# v0_1.net
KiCad netlist of a schematic drawn in EAGLE
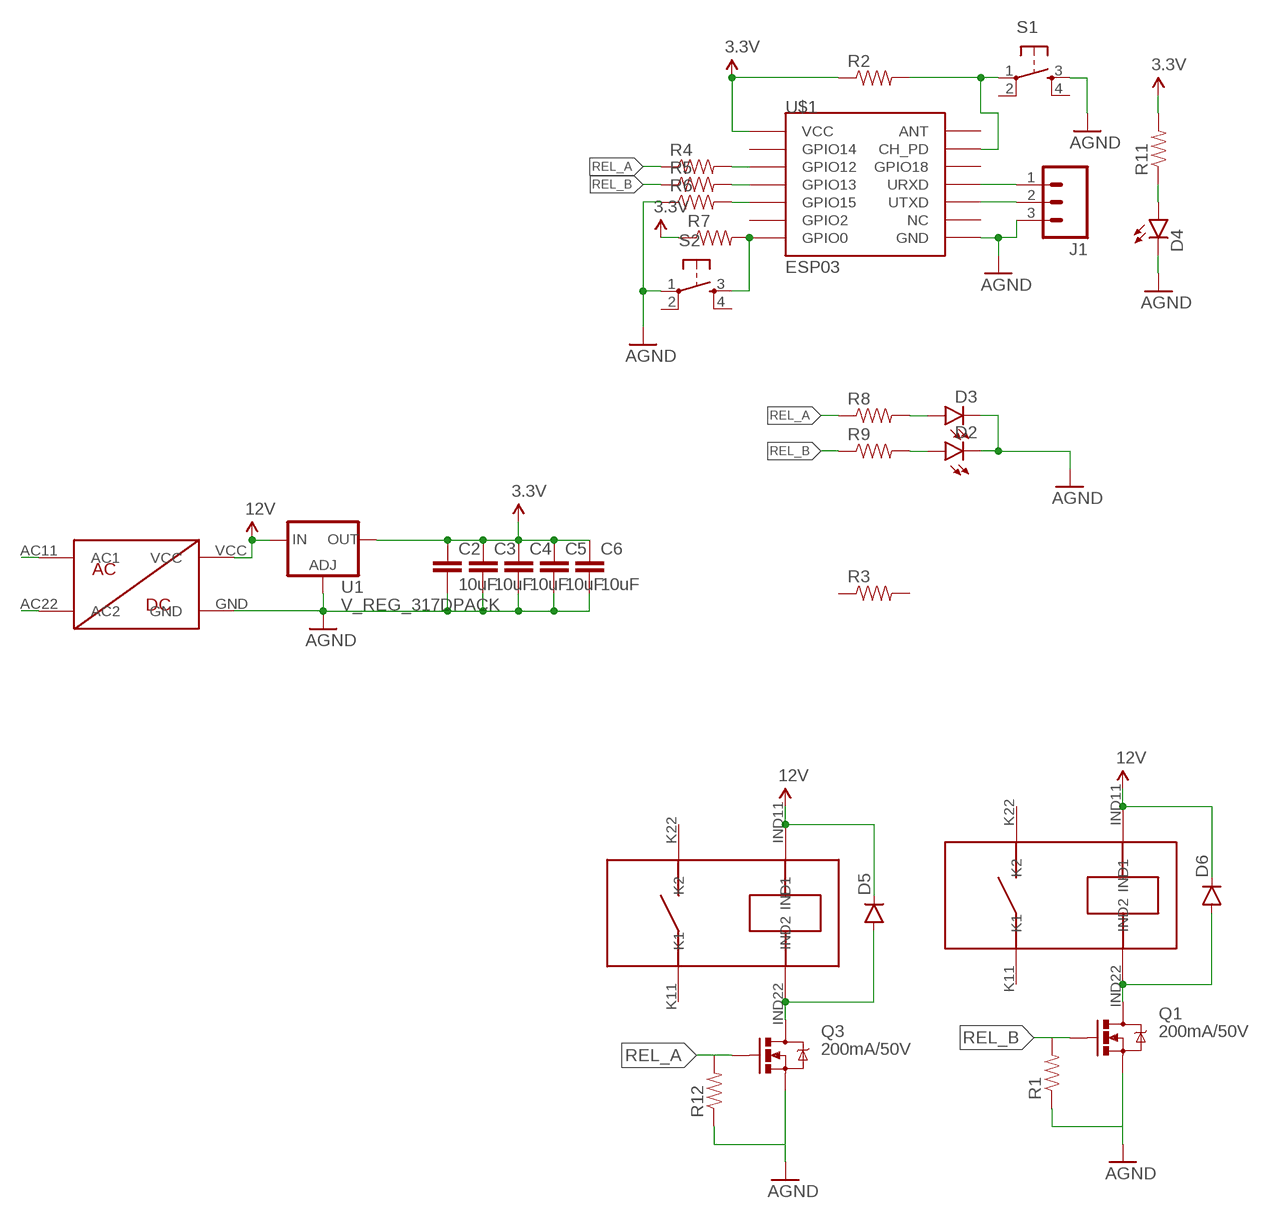
[diagram p0: schematic, sheet 1]

(export (version "E")
  (design (tool "Eeschema 10.0.6"))
  (components
    (comp (ref "C2")
      (value "10uF")
      (footprint "eagle-import:0603-CAP")
      (libsource (lib "eagle-import") (part "10UF-6.3V-20%(0603)"))
    )
    (comp (ref "C3")
      (value "10uF")
      (footprint "eagle-import:0603-CAP")
      (libsource (lib "eagle-import") (part "10UF-6.3V-20%(0603)"))
    )
    (comp (ref "C4")
      (value "10uF")
      (footprint "eagle-import:0603-CAP")
      (libsource (lib "eagle-import") (part "10UF-6.3V-20%(0603)"))
    )
    (comp (ref "C5")
      (value "10uF")
      (footprint "eagle-import:0603-CAP")
      (libsource (lib "eagle-import") (part "10UF-6.3V-20%(0603)"))
    )
    (comp (ref "C6")
      (value "10uF")
      (footprint "eagle-import:0603-CAP")
      (libsource (lib "eagle-import") (part "10UF-6.3V-20%(0603)"))
    )
    (comp (ref "D2")
      (value "LED0603")
      (footprint "eagle-import:LED-0603")
      (libsource (lib "eagle-import") (part "LED0603"))
    )
    (comp (ref "D3")
      (value "LED0603")
      (footprint "eagle-import:LED-0603")
      (libsource (lib "eagle-import") (part "LED0603"))
    )
    (comp (ref "D4")
      (value "LED0603")
      (footprint "eagle-import:LED-0603")
      (libsource (lib "eagle-import") (part "LED0603"))
    )
    (comp (ref "D5")
      (value "DIODESOD123")
      (footprint "eagle-import:SOD-123")
      (libsource (lib "eagle-import") (part "DIODESOD123"))
    )
    (comp (ref "D6")
      (value "DIODESOD123")
      (footprint "eagle-import:SOD-123")
      (libsource (lib "eagle-import") (part "DIODESOD123"))
    )
    (comp (ref "J1")
      (value "M03LONGPADS")
      (footprint "eagle-import:1X03_LONGPADS")
      (libsource (lib "eagle-import") (part "M03LONGPADS"))
    )
    (comp (ref "Q1")
      (value "200mA/50V")
      (footprint "eagle-import:SOT23-3")
      (libsource (lib "eagle-import") (part "MOSFET-NCHANNELBSS138"))
    )
    (comp (ref "Q3")
      (value "200mA/50V")
      (footprint "eagle-import:SOT23-3")
      (libsource (lib "eagle-import") (part "MOSFET-NCHANNELBSS138"))
    )
    (comp (ref "R1")
      (value "RESISTOR0805-RES")
      (footprint "eagle-import:0805")
      (libsource (lib "eagle-import") (part "RESISTOR0805-RES"))
    )
    (comp (ref "R2")
      (value "RESISTOR0805-RES")
      (footprint "eagle-import:0805")
      (libsource (lib "eagle-import") (part "RESISTOR0805-RES"))
    )
    (comp (ref "R3")
      (value "RESISTOR0805-RES")
      (footprint "eagle-import:0805")
      (libsource (lib "eagle-import") (part "RESISTOR0805-RES"))
    )
    (comp (ref "R4")
      (value "RESISTOR0805-RES")
      (footprint "eagle-import:0805")
      (libsource (lib "eagle-import") (part "RESISTOR0805-RES"))
    )
    (comp (ref "R5")
      (value "RESISTOR0805-RES")
      (footprint "eagle-import:0805")
      (libsource (lib "eagle-import") (part "RESISTOR0805-RES"))
    )
    (comp (ref "R6")
      (value "RESISTOR0805-RES")
      (footprint "eagle-import:0805")
      (libsource (lib "eagle-import") (part "RESISTOR0805-RES"))
    )
    (comp (ref "R7")
      (value "RESISTOR0805-RES")
      (footprint "eagle-import:0805")
      (libsource (lib "eagle-import") (part "RESISTOR0805-RES"))
    )
    (comp (ref "R8")
      (value "RESISTOR0805-RES")
      (footprint "eagle-import:0805")
      (libsource (lib "eagle-import") (part "RESISTOR0805-RES"))
    )
    (comp (ref "R9")
      (value "RESISTOR0805-RES")
      (footprint "eagle-import:0805")
      (libsource (lib "eagle-import") (part "RESISTOR0805-RES"))
    )
    (comp (ref "R11")
      (value "RESISTOR0805-RES")
      (footprint "eagle-import:0805")
      (libsource (lib "eagle-import") (part "RESISTOR0805-RES"))
    )
    (comp (ref "R12")
      (value "RESISTOR0805-RES")
      (footprint "eagle-import:0805")
      (libsource (lib "eagle-import") (part "RESISTOR0805-RES"))
    )
    (comp (ref "S1")
      (value "TAC_SWITCHPTH")
      (footprint "eagle-import:TACTILE-PTH")
      (libsource (lib "eagle-import") (part "TAC_SWITCHPTH"))
    )
    (comp (ref "S2")
      (value "TAC_SWITCHPTH")
      (footprint "eagle-import:TACTILE-PTH")
      (libsource (lib "eagle-import") (part "TAC_SWITCHPTH"))
    )
    (comp (ref "U$1")
      (value "ESP03")
      (footprint "eagle-import:ESP03")
      (libsource (lib "eagle-import") (part "ESP03"))
    )
    (comp (ref "U$8")
      (value "ACDC12V350MA")
      (footprint "eagle-import:ACDC12V350MA")
      (libsource (lib "eagle-import") (part "ACDC12V350MA"))
    )
    (comp (ref "U$9")
      (value "302WP")
      (footprint "eagle-import:302WP")
      (libsource (lib "eagle-import") (part "302WP"))
    )
    (comp (ref "U$10")
      (value "302WP")
      (footprint "eagle-import:302WP")
      (libsource (lib "eagle-import") (part "302WP"))
    )
    (comp (ref "U1")
      (value "V_REG_317DPACK")
      (footprint "eagle-import:V-REG_DPACK")
      (libsource (lib "eagle-import") (part "V_REG_317DPACK"))
    )
  )
  (nets
    (net (code "1") (name "3.3V") (class "Default")
      (node (ref "C2") (pin "1") (pinfunction "1_1") (pintype "passive"))
      (node (ref "C3") (pin "1") (pinfunction "1_1") (pintype "passive"))
      (node (ref "C4") (pin "1") (pinfunction "1_1") (pintype "passive"))
      (node (ref "C5") (pin "1") (pinfunction "1_1") (pintype "passive"))
      (node (ref "C6") (pin "1") (pinfunction "1_1") (pintype "passive"))
      (node (ref "R11") (pin "2") (pinfunction "2_2") (pintype "passive"))
      (node (ref "R2") (pin "1") (pinfunction "1_1") (pintype "passive"))
      (node (ref "R7") (pin "1") (pinfunction "1_1") (pintype "passive"))
      (node (ref "U$1") (pin "VCC") (pinfunction "VCC_VCC") (pintype "bidirectional"))
      (node (ref "U1") (pin "4") (pinfunction "OUT_4") (pintype "output"))
    )
    (net (code "2") (name "12V") (class "Default")
      (node (ref "D5") (pin "C") (pinfunction "C_C") (pintype "passive"))
      (node (ref "D6") (pin "C") (pinfunction "C_C") (pintype "passive"))
      (node (ref "U$10") (pin "IND11") (pinfunction "IND1_IND11") (pintype "bidirectional"))
      (node (ref "U$8") (pin "VCC") (pinfunction "VCC_VCC") (pintype "bidirectional"))
      (node (ref "U$9") (pin "IND11") (pinfunction "IND1_IND11") (pintype "bidirectional"))
      (node (ref "U1") (pin "3") (pinfunction "IN_3") (pintype "input"))
    )
    (net (code "3") (name "AGND") (class "Default")
      (node (ref "C2") (pin "2") (pinfunction "2_2") (pintype "passive"))
      (node (ref "C3") (pin "2") (pinfunction "2_2") (pintype "passive"))
      (node (ref "C4") (pin "2") (pinfunction "2_2") (pintype "passive"))
      (node (ref "C5") (pin "2") (pinfunction "2_2") (pintype "passive"))
      (node (ref "C6") (pin "2") (pinfunction "2_2") (pintype "passive"))
      (node (ref "D2") (pin "C") (pinfunction "C_C") (pintype "passive"))
      (node (ref "D3") (pin "C") (pinfunction "C_C") (pintype "passive"))
      (node (ref "D4") (pin "C") (pinfunction "C_C") (pintype "passive"))
      (node (ref "J1") (pin "3") (pinfunction "3_3") (pintype "passive"))
      (node (ref "Q1") (pin "2") (pinfunction "S_2") (pintype "passive"))
      (node (ref "Q3") (pin "2") (pinfunction "S_2") (pintype "passive"))
      (node (ref "R1") (pin "1") (pinfunction "1_1") (pintype "passive"))
      (node (ref "R12") (pin "1") (pinfunction "1_1") (pintype "passive"))
      (node (ref "R6") (pin "1") (pinfunction "1_1") (pintype "passive"))
      (node (ref "S1") (pin "3") (pinfunction "3_3") (pintype "passive"))
      (node (ref "S2") (pin "1") (pinfunction "1_1") (pintype "passive"))
      (node (ref "U$1") (pin "GND") (pinfunction "GND_GND") (pintype "bidirectional"))
      (node (ref "U$8") (pin "GND") (pinfunction "GND_GND") (pintype "bidirectional"))
      (node (ref "U1") (pin "1") (pinfunction "ADJ_1") (pintype "input"))
    )
    (net (code "4") (name "Net-(D2-PadA)") (class "Default")
      (node (ref "D2") (pin "A") (pinfunction "A_A") (pintype "passive"))
      (node (ref "R9") (pin "2") (pinfunction "2_2") (pintype "passive"))
    )
    (net (code "5") (name "Net-(D3-PadA)") (class "Default")
      (node (ref "D3") (pin "A") (pinfunction "A_A") (pintype "passive"))
      (node (ref "R8") (pin "2") (pinfunction "2_2") (pintype "passive"))
    )
    (net (code "6") (name "Net-(D4-PadA)") (class "Default")
      (node (ref "D4") (pin "A") (pinfunction "A_A") (pintype "passive"))
      (node (ref "R11") (pin "1") (pinfunction "1_1") (pintype "passive"))
    )
    (net (code "7") (name "Net-(J1-Pad1)") (class "Default")
      (node (ref "J1") (pin "1") (pinfunction "1_1") (pintype "passive"))
      (node (ref "U$1") (pin "URXD") (pinfunction "URXD_URXD") (pintype "bidirectional"))
    )
    (net (code "8") (name "Net-(J1-Pad2)") (class "Default")
      (node (ref "J1") (pin "2") (pinfunction "2_2") (pintype "passive"))
      (node (ref "U$1") (pin "UTXD") (pinfunction "UTXD_UTXD") (pintype "bidirectional"))
    )
    (net (code "9") (name "Net-(Q1-D)") (class "Default")
      (node (ref "D6") (pin "A") (pinfunction "A_A") (pintype "passive"))
      (node (ref "Q1") (pin "3") (pinfunction "D_3") (pintype "passive"))
      (node (ref "U$9") (pin "IND22") (pinfunction "IND2_IND22") (pintype "bidirectional"))
    )
    (net (code "10") (name "Net-(Q3-D)") (class "Default")
      (node (ref "D5") (pin "A") (pinfunction "A_A") (pintype "passive"))
      (node (ref "Q3") (pin "3") (pinfunction "D_3") (pintype "passive"))
      (node (ref "U$10") (pin "IND22") (pinfunction "IND2_IND22") (pintype "bidirectional"))
    )
    (net (code "11") (name "Net-(R2-Pad2)") (class "Default")
      (node (ref "R2") (pin "2") (pinfunction "2_2") (pintype "passive"))
      (node (ref "S1") (pin "1") (pinfunction "1_1") (pintype "passive"))
      (node (ref "U$1") (pin "CH_PD") (pinfunction "CH_PD_CH_PD") (pintype "bidirectional"))
    )
    (net (code "12") (name "Net-(R4-Pad2)") (class "Default")
      (node (ref "R4") (pin "2") (pinfunction "2_2") (pintype "passive"))
      (node (ref "U$1") (pin "GPIO12") (pinfunction "GPIO12_GPIO12") (pintype "bidirectional"))
    )
    (net (code "13") (name "Net-(R5-Pad2)") (class "Default")
      (node (ref "R5") (pin "2") (pinfunction "2_2") (pintype "passive"))
      (node (ref "U$1") (pin "GPIO13") (pinfunction "GPIO13_GPIO13") (pintype "bidirectional"))
    )
    (net (code "14") (name "Net-(R6-Pad2)") (class "Default")
      (node (ref "R6") (pin "2") (pinfunction "2_2") (pintype "passive"))
      (node (ref "U$1") (pin "GPIO15") (pinfunction "GPIO15_GPIO15") (pintype "bidirectional"))
    )
    (net (code "15") (name "Net-(R7-Pad2)") (class "Default")
      (node (ref "R7") (pin "2") (pinfunction "2_2") (pintype "passive"))
      (node (ref "S2") (pin "3") (pinfunction "3_3") (pintype "passive"))
      (node (ref "U$1") (pin "GPIO0") (pinfunction "GPIO0_GPIO0") (pintype "bidirectional"))
    )
    (net (code "16") (name "REL_A") (class "Default")
      (node (ref "Q3") (pin "1") (pinfunction "G_1") (pintype "passive"))
      (node (ref "R12") (pin "2") (pinfunction "2_2") (pintype "passive"))
      (node (ref "R4") (pin "1") (pinfunction "1_1") (pintype "passive"))
      (node (ref "R8") (pin "1") (pinfunction "1_1") (pintype "passive"))
    )
    (net (code "17") (name "REL_B") (class "Default")
      (node (ref "Q1") (pin "1") (pinfunction "G_1") (pintype "passive"))
      (node (ref "R1") (pin "2") (pinfunction "2_2") (pintype "passive"))
      (node (ref "R5") (pin "1") (pinfunction "1_1") (pintype "passive"))
      (node (ref "R9") (pin "1") (pinfunction "1_1") (pintype "passive"))
    )
    (net (code "18") (name "unconnected-(R3-Pad1)") (class "Default")
      (node (ref "R3") (pin "1") (pinfunction "1_1") (pintype "passive"))
    )
    (net (code "19") (name "unconnected-(R3-Pad2)") (class "Default")
      (node (ref "R3") (pin "2") (pinfunction "2_2") (pintype "passive"))
    )
    (net (code "20") (name "unconnected-(S1-Pad2)") (class "Default")
      (node (ref "S1") (pin "2") (pinfunction "2_2") (pintype "passive"))
    )
    (net (code "21") (name "unconnected-(S1-Pad4)") (class "Default")
      (node (ref "S1") (pin "4") (pinfunction "4_4") (pintype "passive"))
    )
    (net (code "22") (name "unconnected-(S2-Pad2)") (class "Default")
      (node (ref "S2") (pin "2") (pinfunction "2_2") (pintype "passive"))
    )
    (net (code "23") (name "unconnected-(S2-Pad4)") (class "Default")
      (node (ref "S2") (pin "4") (pinfunction "4_4") (pintype "passive"))
    )
    (net (code "24") (name "unconnected-(U$1-PadANT)") (class "Default")
      (node (ref "U$1") (pin "ANT") (pinfunction "ANT_ANT") (pintype "bidirectional"))
    )
    (net (code "25") (name "unconnected-(U$1-PadGPIO2)") (class "Default")
      (node (ref "U$1") (pin "GPIO2") (pinfunction "GPIO2_GPIO2") (pintype "bidirectional"))
    )
    (net (code "26") (name "unconnected-(U$1-PadGPIO14)") (class "Default")
      (node (ref "U$1") (pin "GPIO14") (pinfunction "GPIO14_GPIO14") (pintype "bidirectional"))
    )
    (net (code "27") (name "unconnected-(U$1-PadGPIO18)") (class "Default")
      (node (ref "U$1") (pin "GPIO18") (pinfunction "GPIO18_GPIO18") (pintype "bidirectional"))
    )
    (net (code "28") (name "unconnected-(U$1-PadNC)") (class "Default")
      (node (ref "U$1") (pin "NC") (pinfunction "NC_NC") (pintype "bidirectional"))
    )
    (net (code "29") (name "unconnected-(U$8-AC1-PadAC11)") (class "Default")
      (node (ref "U$8") (pin "AC11") (pinfunction "AC1_AC11") (pintype "bidirectional"))
    )
    (net (code "30") (name "unconnected-(U$8-AC2-PadAC22)") (class "Default")
      (node (ref "U$8") (pin "AC22") (pinfunction "AC2_AC22") (pintype "bidirectional"))
    )
    (net (code "31") (name "unconnected-(U$9-K1-PadK11)") (class "Default")
      (node (ref "U$9") (pin "K11") (pinfunction "K1_K11") (pintype "bidirectional"))
    )
    (net (code "32") (name "unconnected-(U$9-K2-PadK22)") (class "Default")
      (node (ref "U$9") (pin "K22") (pinfunction "K2_K22") (pintype "bidirectional"))
    )
    (net (code "33") (name "unconnected-(U$10-K1-PadK11)") (class "Default")
      (node (ref "U$10") (pin "K11") (pinfunction "K1_K11") (pintype "bidirectional"))
    )
    (net (code "34") (name "unconnected-(U$10-K2-PadK22)") (class "Default")
      (node (ref "U$10") (pin "K22") (pinfunction "K2_K22") (pintype "bidirectional"))
    )
  )
)
